# power.net
KiCad netlist of a schematic drawn in Altium Designer
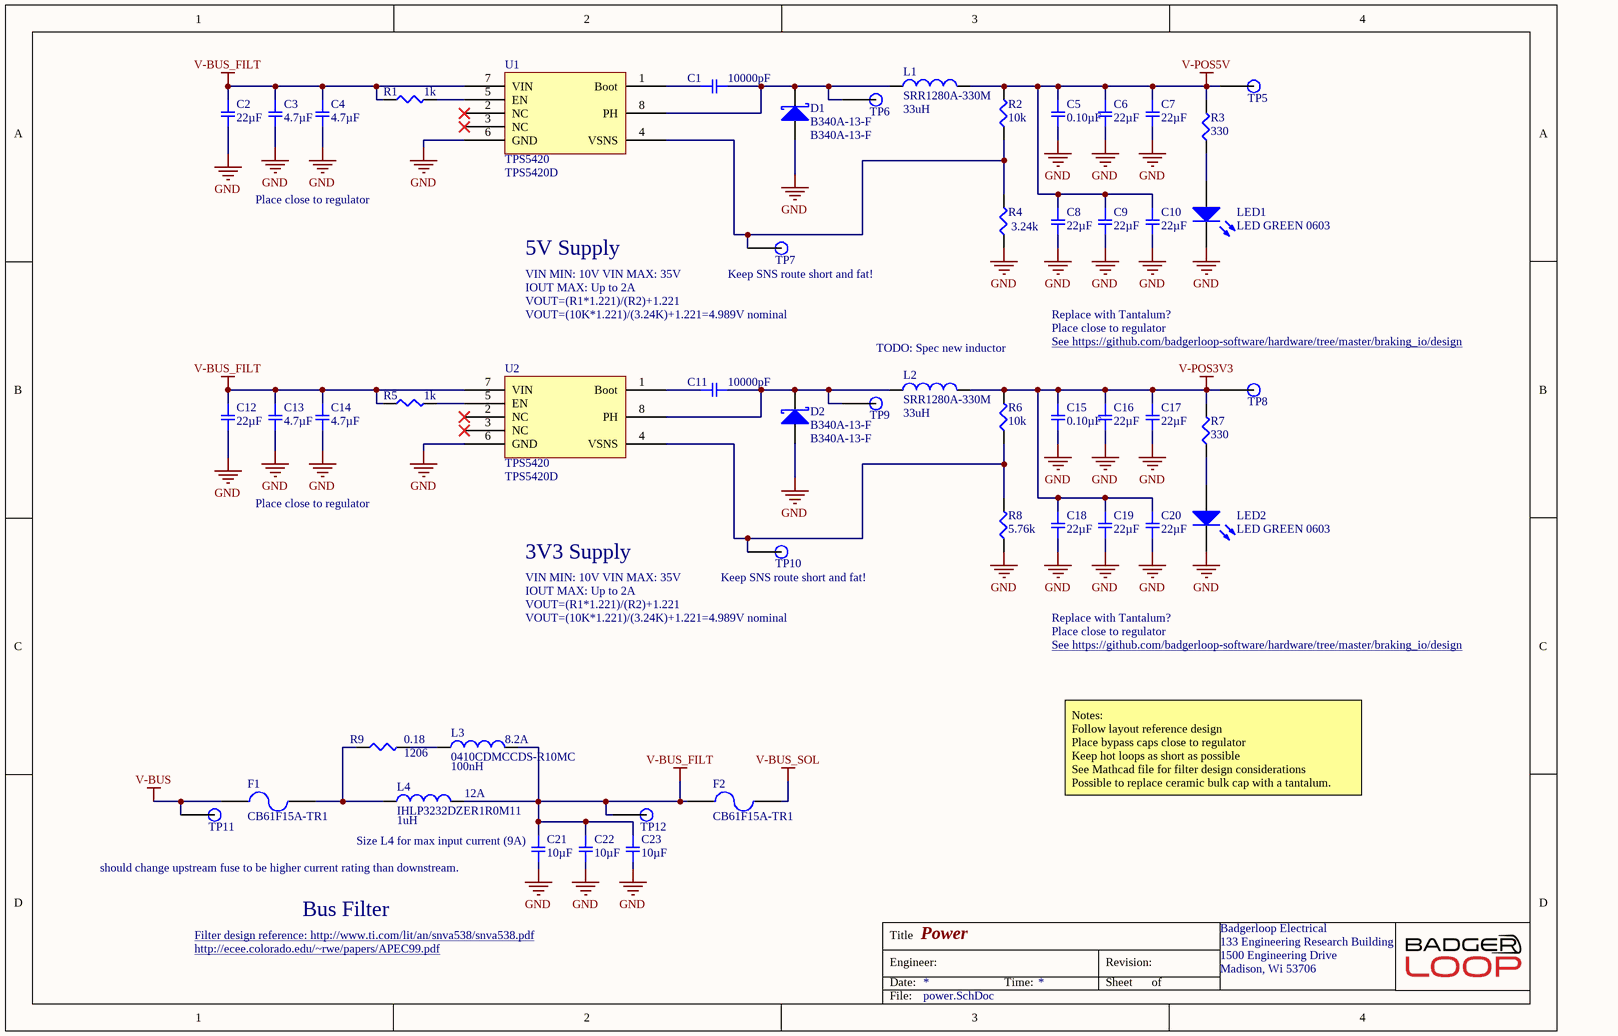
[diagram p0: power.SchDoc]

(export (version "E")
  (design (tool "Eeschema 10.0.6"))
  (components
    (comp (ref "C1")
      (value "10000pF")
      (footprint "SMD-0805C")
      (description "CAP CER 10000PF 250V X7T 0805")
      (fields
        (field (name "DIGI-KEY PART NUMBER") "490-13986-1-ND")
        (field (name "PART NUMBER") "GC321AD72E103KX01D")
      )
      (libsource (lib "capacitors") (part "GC321AD72E103KX01D"))
    )
    (comp (ref "C2")
      (value "22µF")
      (footprint "SMD-1206C")
      (description "CAP CER 22UF 25V X5R 1206")
      (fields
        (field (name "DIGI-KEY PART NUMBER") "490-12451-1-ND")
        (field (name "PART NUMBER") "GRT31CR61E226ME01L")
      )
      (libsource (lib "capacitors") (part "GRT31CR61E226ME01L"))
    )
    (comp (ref "C3")
      (value "4.7µF")
      (footprint "SMD-1206C")
      (description "CAP CER 4.7UF 50V X7S 1206")
      (fields
        (field (name "DIGI-KEY PART NUMBER") "490-11167-1-ND")
        (field (name "PART NUMBER") "GCM31CC71H475KA03L")
      )
      (libsource (lib "capacitors") (part "GCM31CC71H475KA03L"))
    )
    (comp (ref "C4")
      (value "4.7µF")
      (footprint "SMD-1206C")
      (description "CAP CER 4.7UF 50V X7S 1206")
      (fields
        (field (name "DIGI-KEY PART NUMBER") "490-11167-1-ND")
        (field (name "PART NUMBER") "GCM31CC71H475KA03L")
      )
      (libsource (lib "capacitors") (part "GCM31CC71H475KA03L"))
    )
    (comp (ref "C5")
      (value "0.10µF")
      (footprint "SMD-0805C")
      (description "CAP CER 0.1UF 10V U2J 0805")
      (fields
        (field (name "DIGI-KEY PART NUMBER") "490-11592-1-ND")
        (field (name "PART NUMBER") "GRM21B7U1A104JA01L")
      )
      (libsource (lib "capacitors") (part "GRM21B7U1A104JA01L"))
    )
    (comp (ref "C6")
      (value "22µF")
      (footprint "SMD-1206C")
      (description "CAP CER 22UF 25V X5R 1206")
      (fields
        (field (name "DIGI-KEY PART NUMBER") "490-12451-1-ND")
        (field (name "PART NUMBER") "GRT31CR61E226ME01L")
      )
      (libsource (lib "capacitors") (part "GRT31CR61E226ME01L"))
    )
    (comp (ref "C7")
      (value "22µF")
      (footprint "SMD-1206C")
      (description "CAP CER 22UF 25V X5R 1206")
      (fields
        (field (name "DIGI-KEY PART NUMBER") "490-12451-1-ND")
        (field (name "PART NUMBER") "GRT31CR61E226ME01L")
      )
      (libsource (lib "capacitors") (part "GRT31CR61E226ME01L"))
    )
    (comp (ref "C8")
      (value "22µF")
      (footprint "SMD-1206C")
      (description "CAP CER 22UF 25V X5R 1206")
      (fields
        (field (name "DIGI-KEY PART NUMBER") "490-12451-1-ND")
        (field (name "PART NUMBER") "GRT31CR61E226ME01L")
      )
      (libsource (lib "capacitors") (part "GRT31CR61E226ME01L"))
    )
    (comp (ref "C9")
      (value "22µF")
      (footprint "SMD-1206C")
      (description "CAP CER 22UF 25V X5R 1206")
      (fields
        (field (name "DIGI-KEY PART NUMBER") "490-12451-1-ND")
        (field (name "PART NUMBER") "GRT31CR61E226ME01L")
      )
      (libsource (lib "capacitors") (part "GRT31CR61E226ME01L"))
    )
    (comp (ref "C10")
      (value "22µF")
      (footprint "SMD-1206C")
      (description "CAP CER 22UF 25V X5R 1206")
      (fields
        (field (name "DIGI-KEY PART NUMBER") "490-12451-1-ND")
        (field (name "PART NUMBER") "GRT31CR61E226ME01L")
      )
      (libsource (lib "capacitors") (part "GRT31CR61E226ME01L"))
    )
    (comp (ref "C11")
      (value "10000pF")
      (footprint "SMD-0805C")
      (description "CAP CER 10000PF 250V X7T 0805")
      (fields
        (field (name "DIGI-KEY PART NUMBER") "490-13986-1-ND")
        (field (name "PART NUMBER") "GC321AD72E103KX01D")
      )
      (libsource (lib "capacitors") (part "GC321AD72E103KX01D"))
    )
    (comp (ref "C12")
      (value "22µF")
      (footprint "SMD-1206C")
      (description "CAP CER 22UF 25V X5R 1206")
      (fields
        (field (name "DIGI-KEY PART NUMBER") "490-12451-1-ND")
        (field (name "PART NUMBER") "GRT31CR61E226ME01L")
      )
      (libsource (lib "capacitors") (part "GRT31CR61E226ME01L"))
    )
    (comp (ref "C13")
      (value "4.7µF")
      (footprint "SMD-1206C")
      (description "CAP CER 4.7UF 50V X7S 1206")
      (fields
        (field (name "DIGI-KEY PART NUMBER") "490-11167-1-ND")
        (field (name "PART NUMBER") "GCM31CC71H475KA03L")
      )
      (libsource (lib "capacitors") (part "GCM31CC71H475KA03L"))
    )
    (comp (ref "C14")
      (value "4.7µF")
      (footprint "SMD-1206C")
      (description "CAP CER 4.7UF 50V X7S 1206")
      (fields
        (field (name "DIGI-KEY PART NUMBER") "490-11167-1-ND")
        (field (name "PART NUMBER") "GCM31CC71H475KA03L")
      )
      (libsource (lib "capacitors") (part "GCM31CC71H475KA03L"))
    )
    (comp (ref "C15")
      (value "0.10µF")
      (footprint "SMD-0805C")
      (description "CAP CER 0.1UF 10V U2J 0805")
      (fields
        (field (name "DIGI-KEY PART NUMBER") "490-11592-1-ND")
        (field (name "PART NUMBER") "GRM21B7U1A104JA01L")
      )
      (libsource (lib "capacitors") (part "GRM21B7U1A104JA01L"))
    )
    (comp (ref "C16")
      (value "22µF")
      (footprint "SMD-1206C")
      (description "CAP CER 22UF 25V X5R 1206")
      (fields
        (field (name "DIGI-KEY PART NUMBER") "490-12451-1-ND")
        (field (name "PART NUMBER") "GRT31CR61E226ME01L")
      )
      (libsource (lib "capacitors") (part "GRT31CR61E226ME01L"))
    )
    (comp (ref "C17")
      (value "22µF")
      (footprint "SMD-1206C")
      (description "CAP CER 22UF 25V X5R 1206")
      (fields
        (field (name "DIGI-KEY PART NUMBER") "490-12451-1-ND")
        (field (name "PART NUMBER") "GRT31CR61E226ME01L")
      )
      (libsource (lib "capacitors") (part "GRT31CR61E226ME01L"))
    )
    (comp (ref "C18")
      (value "22µF")
      (footprint "SMD-1206C")
      (description "CAP CER 22UF 25V X5R 1206")
      (fields
        (field (name "DIGI-KEY PART NUMBER") "490-12451-1-ND")
        (field (name "PART NUMBER") "GRT31CR61E226ME01L")
      )
      (libsource (lib "capacitors") (part "GRT31CR61E226ME01L"))
    )
    (comp (ref "C19")
      (value "22µF")
      (footprint "SMD-1206C")
      (description "CAP CER 22UF 25V X5R 1206")
      (fields
        (field (name "DIGI-KEY PART NUMBER") "490-12451-1-ND")
        (field (name "PART NUMBER") "GRT31CR61E226ME01L")
      )
      (libsource (lib "capacitors") (part "GRT31CR61E226ME01L"))
    )
    (comp (ref "C20")
      (value "22µF")
      (footprint "SMD-1206C")
      (description "CAP CER 22UF 25V X5R 1206")
      (fields
        (field (name "DIGI-KEY PART NUMBER") "490-12451-1-ND")
        (field (name "PART NUMBER") "GRT31CR61E226ME01L")
      )
      (libsource (lib "capacitors") (part "GRT31CR61E226ME01L"))
    )
    (comp (ref "C21")
      (value "10µF")
      (footprint "SMD-1206C")
      (description "CAP CER 10UF 50V X5R 1206")
      (fields
        (field (name "DIGI-KEY PART NUMBER") "490-12457-1-ND")
        (field (name "PART NUMBER") "GRT31CR61H106ME01L")
      )
      (libsource (lib "capacitors") (part "GRT31CR61H106ME01L"))
    )
    (comp (ref "C22")
      (value "10µF")
      (footprint "SMD-1206C")
      (description "CAP CER 10UF 50V X5R 1206")
      (fields
        (field (name "DIGI-KEY PART NUMBER") "490-12457-1-ND")
        (field (name "PART NUMBER") "GRT31CR61H106ME01L")
      )
      (libsource (lib "capacitors") (part "GRT31CR61H106ME01L"))
    )
    (comp (ref "C23")
      (value "10µF")
      (footprint "SMD-1206C")
      (description "CAP CER 10UF 50V X5R 1206")
      (fields
        (field (name "DIGI-KEY PART NUMBER") "490-12457-1-ND")
        (field (name "PART NUMBER") "GRT31CR61H106ME01L")
      )
      (libsource (lib "capacitors") (part "GRT31CR61H106ME01L"))
    )
    (comp (ref "D1")
      (value "B340A-13-F")
      (footprint "DIOM4326X20N")
      (description "DIODE SCHOTTKY 40V 3A SMA")
      (fields
        (field (name "MANUFACTURER") "Diodes")
        (field (name "VOLTAGE") "40V")
        (field (name "MANUFACTURER PART NUMBER") "B340A-13-F")
      )
      (libsource (lib "misc") (part "B340A-13-F"))
    )
    (comp (ref "D2")
      (value "B340A-13-F")
      (footprint "DIOM4326X20N")
      (description "DIODE SCHOTTKY 40V 3A SMA")
      (fields
        (field (name "MANUFACTURER") "Diodes")
        (field (name "VOLTAGE") "40V")
        (field (name "MANUFACTURER PART NUMBER") "B340A-13-F")
      )
      (libsource (lib "misc") (part "B340A-13-F"))
    )
    (comp (ref "F1")
      (value "CB61F15A-TR1")
      (footprint "RESC6132X26N")
      (fields (field (name "MANUFACTURER") "Eaton"))
      (libsource (lib "misc") (part "CB61F15A-TR1"))
    )
    (comp (ref "F2")
      (value "CB61F15A-TR1")
      (footprint "RESC6132X26N")
      (fields (field (name "MANUFACTURER") "Eaton"))
      (libsource (lib "misc") (part "CB61F15A-TR1"))
    )
    (comp (ref "L1")
      (value "SRR1280A-330M")
      (footprint "INDM120125X75N")
      (description "Inductor Power Shielded Wirewound 33uH 20% 1KHz 28Q-Factor Ferrite 3.5A 57mOhm DCR Automotive T/R")
      (fields
        (field (name "MANUFACTURER") "Bourns")
        (field (name "TOLERANCE") "20%")
        (field (name "INDUCTANCE") "33uH")
      )
      (libsource (lib "misc") (part "SRR1280A-330M"))
    )
    (comp (ref "L2")
      (value "SRR1280A-330M")
      (footprint "INDM120125X75N")
      (description "Inductor Power Shielded Wirewound 33uH 20% 1KHz 28Q-Factor Ferrite 3.5A 57mOhm DCR Automotive T/R")
      (fields
        (field (name "MANUFACTURER") "Bourns")
        (field (name "TOLERANCE") "20%")
        (field (name "INDUCTANCE") "33uH")
      )
      (libsource (lib "misc") (part "SRR1280A-330M"))
    )
    (comp (ref "L3")
      (value "0410CDMCCDS-R10MC")
      (footprint "INDM4442X20N")
      (fields
        (field (name "MANUFACTURER") "Sumida")
        (field (name "INDUCTANCE") "100nH")
        (field (name "SATURATION CURRENT") "8.2A")
      )
      (libsource (lib "inductor") (part "0410CDMCCDS-R10MC"))
    )
    (comp (ref "L4")
      (value "IHLP3232DZER1R0M11")
      (footprint "INDM8682X40N")
      (description "Fixed Inductors 1uH 20% Low Profile")
      (fields
        (field (name "MANUFACTURER") "Vishay Dale")
        (field (name "TOLERANCE") "20%")
        (field (name "SATURATION CURRENT") "12A")
        (field (name "INDUCTANCE") "1uH")
      )
      (libsource (lib "misc") (part "IHLP3232DZER1R0M11"))
    )
    (comp (ref "LED1")
      (value "LED GREEN 0603")
      (footprint "LED 0603 GREEN")
      (fields (field (name "MANUFACTURER") "Lite-On Inc."))
      (libsource (lib "misc") (part "LED GREEN 0603"))
    )
    (comp (ref "LED2")
      (value "LED GREEN 0603")
      (footprint "LED 0603 GREEN")
      (fields (field (name "MANUFACTURER") "Lite-On Inc."))
      (libsource (lib "misc") (part "LED GREEN 0603"))
    )
    (comp (ref "R1")
      (value "1k")
      (footprint "SMD-0805-RES")
      (description "RES SMD 1K OHM 5% 1/2W 0805")
      (fields
        (field (name "PART NUMBER") "ERJ-P06J102V")
        (field (name "DIGI-KEY PART NUMBER") "P1.0KADCT-ND")
      )
      (libsource (lib "resistors") (part "ERJ-P06J102V"))
    )
    (comp (ref "R2")
      (value "10k")
      (footprint "SMD-0805-RES")
      (description "RES SMD 10K OHM 5% 1/2W 0805")
      (fields (field (name "PART NUMBER") "ERJ-P06J103V") (field (name "DIGI-KEY PART NUMBER") "P10KADCT-ND"))
      (libsource (lib "resistors") (part "ERJ-P06J103V"))
    )
    (comp (ref "R3")
      (value "330")
      (footprint "SMD-0805-RES")
      (description "RES SMD 330 OHM 5% 1/2W 0805")
      (fields (field (name "PART NUMBER") "ERJ-P06J331V") (field (name "DIGI-KEY PART NUMBER") "P330ADCT-ND"))
      (libsource (lib "resistors") (part "ERJ-P06J331V"))
    )
    (comp (ref "R4")
      (value "3.24k")
      (footprint "SMD-0805-RES")
      (description "RES SMD 3.24K OHM 1% 1/8W 0805")
      (fields
        (field (name "PART NUMBER") "ERJ-6ENF3241V")
        (field (name "DIGI-KEY PART NUMBER") "P3.24KCCT-ND")
      )
      (libsource (lib "resistors") (part "ERJ-6ENF3241V"))
    )
    (comp (ref "R5")
      (value "1k")
      (footprint "SMD-0805-RES")
      (description "RES SMD 1K OHM 5% 1/2W 0805")
      (fields
        (field (name "PART NUMBER") "ERJ-P06J102V")
        (field (name "DIGI-KEY PART NUMBER") "P1.0KADCT-ND")
      )
      (libsource (lib "resistors") (part "ERJ-P06J102V"))
    )
    (comp (ref "R6")
      (value "10k")
      (footprint "SMD-0805-RES")
      (description "RES SMD 10K OHM 5% 1/2W 0805")
      (fields (field (name "PART NUMBER") "ERJ-P06J103V") (field (name "DIGI-KEY PART NUMBER") "P10KADCT-ND"))
      (libsource (lib "resistors") (part "ERJ-P06J103V"))
    )
    (comp (ref "R7")
      (value "330")
      (footprint "SMD-0805-RES")
      (description "RES SMD 330 OHM 5% 1/2W 0805")
      (fields (field (name "PART NUMBER") "ERJ-P06J331V") (field (name "DIGI-KEY PART NUMBER") "P330ADCT-ND"))
      (libsource (lib "resistors") (part "ERJ-P06J331V"))
    )
    (comp (ref "R8")
      (value "5.76k")
      (footprint "SMD-0805-RES")
      (description "RES SMD 5.76K OHM 1% 1/8W 0805")
      (fields
        (field (name "PART NUMBER") "ERJ-6ENF5761V")
        (field (name "DIGI-KEY PART NUMBER") "P5.76KCCT-ND")
      )
      (libsource (lib "resistors") (part "ERJ-6ENF5761V"))
    )
    (comp (ref "R9")
      (value "0.18")
      (footprint "SMD-1206-RES")
      (description "RES SMD 0.18 OHM 1% 1/2W 1206")
      (fields
        (field (name "PART NUMBER") "ERJ-8BSFR18V")
        (field (name "DIGI-KEY PART NUMBER") "P17683CT-ND")
        (field (name "SUPPLIER DEVICE PACKAGE") "1206")
      )
      (libsource (lib "resistors") (part "ERJ-8BSFR18V"))
    )
    (comp (ref "TP5")
      (value "TP")
      (footprint "Test Point")
      (description "SMD TEST POINT")
      (libsource (lib "misc") (part "TP"))
    )
    (comp (ref "TP6")
      (value "TP")
      (footprint "Test Point")
      (description "SMD TEST POINT")
      (libsource (lib "misc") (part "TP"))
    )
    (comp (ref "TP7")
      (value "TP")
      (footprint "Test Point")
      (description "SMD TEST POINT")
      (libsource (lib "misc") (part "TP"))
    )
    (comp (ref "TP8")
      (value "TP")
      (footprint "Test Point")
      (description "SMD TEST POINT")
      (libsource (lib "misc") (part "TP"))
    )
    (comp (ref "TP9")
      (value "TP")
      (footprint "Test Point")
      (description "SMD TEST POINT")
      (libsource (lib "misc") (part "TP"))
    )
    (comp (ref "TP10")
      (value "TP")
      (footprint "Test Point")
      (description "SMD TEST POINT")
      (libsource (lib "misc") (part "TP"))
    )
    (comp (ref "TP11")
      (value "TP")
      (footprint "Test Point")
      (description "SMD TEST POINT")
      (libsource (lib "misc") (part "TP"))
    )
    (comp (ref "TP12")
      (value "TP")
      (footprint "Test Point")
      (description "SMD TEST POINT")
      (libsource (lib "misc") (part "TP"))
    )
    (comp (ref "U1")
      (value "TPS5420")
      (footprint "SOP127P600X175-8N")
      (fields
        (field (name "MANUFACTURER") "Texas Instruments")
        (field (name "MANUFACTURER PART NUMBER") "TPS5420D")
      )
      (libsource (lib "ic") (part "TPS5420"))
    )
    (comp (ref "U2")
      (value "TPS5420")
      (footprint "SOP127P600X175-8N")
      (fields
        (field (name "MANUFACTURER") "Texas Instruments")
        (field (name "MANUFACTURER PART NUMBER") "TPS5420D")
      )
      (libsource (lib "ic") (part "TPS5420"))
    )
  )
  (nets
    (net (code "1") (name "GND") (class "Default")
      (node (ref "C10") (pin "2") (pinfunction "2_2") (pintype "passive"))
      (node (ref "C12") (pin "2") (pinfunction "2_2") (pintype "passive"))
      (node (ref "C13") (pin "2") (pinfunction "2_2") (pintype "passive"))
      (node (ref "C14") (pin "2") (pinfunction "2_2") (pintype "passive"))
      (node (ref "C15") (pin "2") (pinfunction "2_2") (pintype "passive"))
      (node (ref "C16") (pin "2") (pinfunction "2_2") (pintype "passive"))
      (node (ref "C17") (pin "2") (pinfunction "2_2") (pintype "passive"))
      (node (ref "C18") (pin "2") (pinfunction "2_2") (pintype "passive"))
      (node (ref "C19") (pin "2") (pinfunction "2_2") (pintype "passive"))
      (node (ref "C2") (pin "2") (pinfunction "2_2") (pintype "passive"))
      (node (ref "C20") (pin "2") (pinfunction "2_2") (pintype "passive"))
      (node (ref "C21") (pin "2") (pinfunction "2_2") (pintype "passive"))
      (node (ref "C22") (pin "2") (pinfunction "2_2") (pintype "passive"))
      (node (ref "C23") (pin "2") (pinfunction "2_2") (pintype "passive"))
      (node (ref "C3") (pin "2") (pinfunction "2_2") (pintype "passive"))
      (node (ref "C4") (pin "2") (pinfunction "2_2") (pintype "passive"))
      (node (ref "C5") (pin "2") (pinfunction "2_2") (pintype "passive"))
      (node (ref "C6") (pin "2") (pinfunction "2_2") (pintype "passive"))
      (node (ref "C7") (pin "2") (pinfunction "2_2") (pintype "passive"))
      (node (ref "C8") (pin "2") (pinfunction "2_2") (pintype "passive"))
      (node (ref "C9") (pin "2") (pinfunction "2_2") (pintype "passive"))
      (node (ref "D1") (pin "1") (pinfunction "A_1") (pintype "passive"))
      (node (ref "D2") (pin "1") (pinfunction "A_1") (pintype "passive"))
      (node (ref "LED1") (pin "2") (pinfunction "K_2") (pintype "passive"))
      (node (ref "LED2") (pin "2") (pinfunction "K_2") (pintype "passive"))
      (node (ref "R4") (pin "1") (pinfunction "1_1") (pintype "passive"))
      (node (ref "R8") (pin "1") (pinfunction "1_1") (pintype "passive"))
      (node (ref "U1") (pin "6") (pinfunction "GND_6") (pintype "passive"))
      (node (ref "U2") (pin "6") (pinfunction "GND_6") (pintype "passive"))
    )
    (net (code "2") (name "Net-(D1-K)") (class "Default")
      (node (ref "C1") (pin "2") (pinfunction "2_2") (pintype "passive"))
      (node (ref "D1") (pin "2") (pinfunction "K_2") (pintype "passive"))
      (node (ref "L1") (pin "1") (pinfunction "1_1") (pintype "passive"))
      (node (ref "TP6") (pin "1") (pinfunction "1_1") (pintype "passive"))
      (node (ref "U1") (pin "8") (pinfunction "PH_8") (pintype "passive"))
    )
    (net (code "3") (name "Net-(D2-K)") (class "Default")
      (node (ref "C11") (pin "2") (pinfunction "2_2") (pintype "passive"))
      (node (ref "D2") (pin "2") (pinfunction "K_2") (pintype "passive"))
      (node (ref "L2") (pin "1") (pinfunction "1_1") (pintype "passive"))
      (node (ref "TP9") (pin "1") (pinfunction "1_1") (pintype "passive"))
      (node (ref "U2") (pin "8") (pinfunction "PH_8") (pintype "passive"))
    )
    (net (code "4") (name "Net-(F1-Pad2)") (class "Default")
      (node (ref "F1") (pin "2") (pinfunction "2_2") (pintype "passive"))
      (node (ref "L4") (pin "1") (pinfunction "1_1") (pintype "passive"))
      (node (ref "R9") (pin "1") (pinfunction "1_1") (pintype "passive"))
    )
    (net (code "5") (name "Net-(L3-Pad1)") (class "Default")
      (node (ref "L3") (pin "1") (pinfunction "1_1") (pintype "passive"))
      (node (ref "R9") (pin "2") (pinfunction "2_2") (pintype "passive"))
    )
    (net (code "6") (name "Net-(LED1-A)") (class "Default")
      (node (ref "LED1") (pin "1") (pinfunction "A_1") (pintype "passive"))
      (node (ref "R3") (pin "1") (pinfunction "1_1") (pintype "passive"))
    )
    (net (code "7") (name "Net-(LED2-A)") (class "Default")
      (node (ref "LED2") (pin "1") (pinfunction "A_1") (pintype "passive"))
      (node (ref "R7") (pin "1") (pinfunction "1_1") (pintype "passive"))
    )
    (net (code "8") (name "Net-(U1-Boot)") (class "Default")
      (node (ref "C1") (pin "1") (pinfunction "1_1") (pintype "passive"))
      (node (ref "U1") (pin "1") (pinfunction "Boot_1") (pintype "passive"))
    )
    (net (code "9") (name "Net-(U1-EN)") (class "Default")
      (node (ref "R1") (pin "2") (pinfunction "2_2") (pintype "passive"))
      (node (ref "U1") (pin "5") (pinfunction "EN_5") (pintype "passive"))
    )
    (net (code "10") (name "Net-(U1-VSNS)") (class "Default")
      (node (ref "R2") (pin "1") (pinfunction "1_1") (pintype "passive"))
      (node (ref "R4") (pin "2") (pinfunction "2_2") (pintype "passive"))
      (node (ref "TP7") (pin "1") (pinfunction "1_1") (pintype "passive"))
      (node (ref "U1") (pin "4") (pinfunction "VSNS_4") (pintype "power_in"))
    )
    (net (code "11") (name "Net-(U2-Boot)") (class "Default")
      (node (ref "C11") (pin "1") (pinfunction "1_1") (pintype "passive"))
      (node (ref "U2") (pin "1") (pinfunction "Boot_1") (pintype "passive"))
    )
    (net (code "12") (name "Net-(U2-EN)") (class "Default")
      (node (ref "R5") (pin "2") (pinfunction "2_2") (pintype "passive"))
      (node (ref "U2") (pin "5") (pinfunction "EN_5") (pintype "passive"))
    )
    (net (code "13") (name "Net-(U2-VSNS)") (class "Default")
      (node (ref "R6") (pin "1") (pinfunction "1_1") (pintype "passive"))
      (node (ref "R8") (pin "2") (pinfunction "2_2") (pintype "passive"))
      (node (ref "TP10") (pin "1") (pinfunction "1_1") (pintype "passive"))
      (node (ref "U2") (pin "4") (pinfunction "VSNS_4") (pintype "power_in"))
    )
    (net (code "14") (name "V-BUS") (class "Default")
      (node (ref "F1") (pin "1") (pinfunction "1_1") (pintype "passive"))
      (node (ref "TP11") (pin "1") (pinfunction "1_1") (pintype "passive"))
    )
    (net (code "15") (name "V-BUS_FILT") (class "Default")
      (node (ref "C12") (pin "1") (pinfunction "1_1") (pintype "passive"))
      (node (ref "C13") (pin "1") (pinfunction "1_1") (pintype "passive"))
      (node (ref "C14") (pin "1") (pinfunction "1_1") (pintype "passive"))
      (node (ref "C2") (pin "1") (pinfunction "1_1") (pintype "passive"))
      (node (ref "C21") (pin "1") (pinfunction "1_1") (pintype "passive"))
      (node (ref "C22") (pin "1") (pinfunction "1_1") (pintype "passive"))
      (node (ref "C23") (pin "1") (pinfunction "1_1") (pintype "passive"))
      (node (ref "C3") (pin "1") (pinfunction "1_1") (pintype "passive"))
      (node (ref "C4") (pin "1") (pinfunction "1_1") (pintype "passive"))
      (node (ref "F2") (pin "1") (pinfunction "1_1") (pintype "passive"))
      (node (ref "L3") (pin "2") (pinfunction "2_2") (pintype "passive"))
      (node (ref "L4") (pin "2") (pinfunction "2_2") (pintype "passive"))
      (node (ref "R1") (pin "1") (pinfunction "1_1") (pintype "passive"))
      (node (ref "R5") (pin "1") (pinfunction "1_1") (pintype "passive"))
      (node (ref "TP12") (pin "1") (pinfunction "1_1") (pintype "passive"))
      (node (ref "U1") (pin "7") (pinfunction "VIN_7") (pintype "passive"))
      (node (ref "U2") (pin "7") (pinfunction "VIN_7") (pintype "passive"))
    )
    (net (code "16") (name "V-BUS_SOL") (class "Default")
      (node (ref "F2") (pin "2") (pinfunction "2_2") (pintype "passive"))
    )
    (net (code "17") (name "V-POS3V3") (class "Default")
      (node (ref "C15") (pin "1") (pinfunction "1_1") (pintype "passive"))
      (node (ref "C16") (pin "1") (pinfunction "1_1") (pintype "passive"))
      (node (ref "C17") (pin "1") (pinfunction "1_1") (pintype "passive"))
      (node (ref "C18") (pin "1") (pinfunction "1_1") (pintype "passive"))
      (node (ref "C19") (pin "1") (pinfunction "1_1") (pintype "passive"))
      (node (ref "C20") (pin "1") (pinfunction "1_1") (pintype "passive"))
      (node (ref "L2") (pin "2") (pinfunction "2_2") (pintype "passive"))
      (node (ref "R6") (pin "2") (pinfunction "2_2") (pintype "passive"))
      (node (ref "R7") (pin "2") (pinfunction "2_2") (pintype "passive"))
      (node (ref "TP8") (pin "1") (pinfunction "1_1") (pintype "passive"))
    )
    (net (code "18") (name "V-POS5V") (class "Default")
      (node (ref "C10") (pin "1") (pinfunction "1_1") (pintype "passive"))
      (node (ref "C5") (pin "1") (pinfunction "1_1") (pintype "passive"))
      (node (ref "C6") (pin "1") (pinfunction "1_1") (pintype "passive"))
      (node (ref "C7") (pin "1") (pinfunction "1_1") (pintype "passive"))
      (node (ref "C8") (pin "1") (pinfunction "1_1") (pintype "passive"))
      (node (ref "C9") (pin "1") (pinfunction "1_1") (pintype "passive"))
      (node (ref "L1") (pin "2") (pinfunction "2_2") (pintype "passive"))
      (node (ref "R2") (pin "2") (pinfunction "2_2") (pintype "passive"))
      (node (ref "R3") (pin "2") (pinfunction "2_2") (pintype "passive"))
      (node (ref "TP5") (pin "1") (pinfunction "1_1") (pintype "passive"))
    )
    (net (code "19") (name "unconnected-(U1-NC-Pad2)") (class "Default")
      (node (ref "U1") (pin "2") (pinfunction "NC_2") (pintype "power_in+no_connect"))
    )
    (net (code "20") (name "unconnected-(U1-NC-Pad3)") (class "Default")
      (node (ref "U1") (pin "3") (pinfunction "NC_3") (pintype "passive+no_connect"))
    )
    (net (code "21") (name "unconnected-(U2-NC-Pad2)") (class "Default")
      (node (ref "U2") (pin "2") (pinfunction "NC_2") (pintype "power_in+no_connect"))
    )
    (net (code "22") (name "unconnected-(U2-NC-Pad3)") (class "Default")
      (node (ref "U2") (pin "3") (pinfunction "NC_3") (pintype "passive+no_connect"))
    )
  )
)
